# load.net
KiCad netlist of a schematic drawn in EAGLE
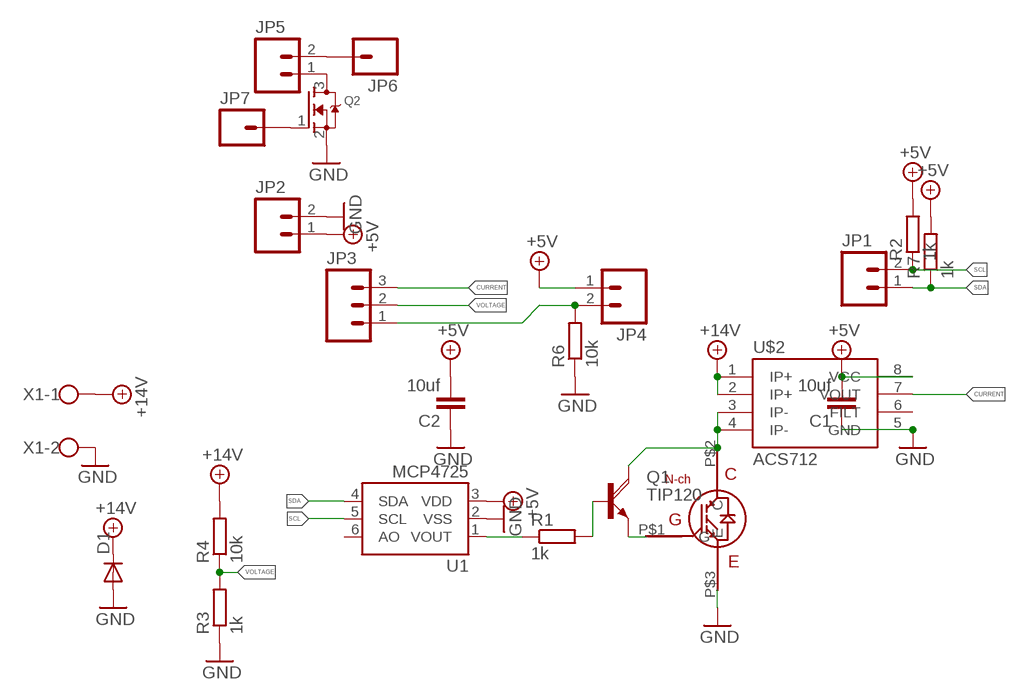
[diagram p0: schematic, sheet 1]

(export (version "E")
  (design (tool "Eeschema 10.0.6"))
  (components
    (comp (ref "C1")
      (value "10uf")
      (footprint "eagle-import:C0603")
      (libsource (lib "eagle-import") (part "C-EUC0603"))
    )
    (comp (ref "C2")
      (value "10uf")
      (footprint "eagle-import:C0603")
      (libsource (lib "eagle-import") (part "C-EUC0603"))
    )
    (comp (ref "D1")
      (value "DIODE-TO220V")
      (footprint "eagle-import:TO220ACS")
      (libsource (lib "eagle-import") (part "DIODE-TO220V"))
    )
    (comp (ref "JP1")
      (value "M02PTH")
      (footprint "eagle-import:1X02")
      (libsource (lib "eagle-import") (part "M02PTH"))
    )
    (comp (ref "JP2")
      (value "M02PTH")
      (footprint "eagle-import:1X02")
      (libsource (lib "eagle-import") (part "M02PTH"))
    )
    (comp (ref "JP3")
      (value "M03PTH")
      (footprint "eagle-import:1X03")
      (libsource (lib "eagle-import") (part "M03PTH"))
    )
    (comp (ref "JP4")
      (value "M02PTH")
      (footprint "eagle-import:1X02")
      (libsource (lib "eagle-import") (part "M02PTH"))
    )
    (comp (ref "JP5")
      (value "M02PTH")
      (footprint "eagle-import:1X02")
      (libsource (lib "eagle-import") (part "M02PTH"))
    )
    (comp (ref "JP6")
      (value "M01PTH")
      (footprint "eagle-import:1X01")
      (libsource (lib "eagle-import") (part "M01PTH"))
    )
    (comp (ref "JP7")
      (value "M01PTH")
      (footprint "eagle-import:1X01")
      (libsource (lib "eagle-import") (part "M01PTH"))
    )
    (comp (ref "Q1")
      (value "TIP120")
      (footprint "eagle-import:TO220AH")
      (libsource (lib "eagle-import") (part "TIP120"))
    )
    (comp (ref "Q2")
      (value "MOSFET-NREFLOW")
      (footprint "eagle-import:SOT23")
      (libsource (lib "eagle-import") (part "MOSFET-NREFLOW"))
    )
    (comp (ref "R1")
      (value "1k")
      (footprint "eagle-import:R0603")
      (libsource (lib "eagle-import") (part "R-EU_R0603"))
    )
    (comp (ref "R2")
      (value "1k")
      (footprint "eagle-import:R0603")
      (libsource (lib "eagle-import") (part "R-EU_R0603"))
    )
    (comp (ref "R3")
      (value "1k")
      (footprint "eagle-import:R0603")
      (libsource (lib "eagle-import") (part "R-EU_R0603"))
    )
    (comp (ref "R4")
      (value "10k")
      (footprint "eagle-import:R0603")
      (libsource (lib "eagle-import") (part "R-EU_R0603"))
    )
    (comp (ref "R6")
      (value "10k")
      (footprint "eagle-import:R0603")
      (libsource (lib "eagle-import") (part "R-EU_R0603"))
    )
    (comp (ref "R7")
      (value "1k")
      (footprint "eagle-import:R0603")
      (libsource (lib "eagle-import") (part "R-EU_R0603"))
    )
    (comp (ref "U$1")
      (value "TO-247A")
      (footprint "eagle-import:TO-247")
      (libsource (lib "eagle-import") (part "TO-247A"))
    )
    (comp (ref "U$2")
      (value "ACS712")
      (footprint "eagle-import:SO08")
      (libsource (lib "eagle-import") (part "ACS712"))
    )
    (comp (ref "U1")
      (value "MCP4725")
      (footprint "eagle-import:SOT23-6")
      (libsource (lib "eagle-import") (part "MCP4725SOT-23"))
    )
    (comp (ref "X1")
      (value "W237-102")
      (footprint "eagle-import:W237-102")
      (fields (field (name "MPN") "237-102"))
      (libsource (lib "eagle-import") (part "W237-102"))
    )
  )
  (nets
    (net (code "1") (name "+5V") (class "Default")
      (node (ref "C1") (pin "2") (pinfunction "2_2") (pintype "passive"))
      (node (ref "C2") (pin "2") (pinfunction "2_2") (pintype "passive"))
      (node (ref "JP2") (pin "1") (pinfunction "1_1") (pintype "passive"))
      (node (ref "JP4") (pin "1") (pinfunction "1_1") (pintype "passive"))
      (node (ref "R2") (pin "2") (pinfunction "2_2") (pintype "passive"))
      (node (ref "R7") (pin "2") (pinfunction "2_2") (pintype "passive"))
      (node (ref "U$2") (pin "8") (pinfunction "VCC_8") (pintype "bidirectional"))
      (node (ref "U1") (pin "3") (pinfunction "VDD_3") (pintype "bidirectional"))
    )
    (net (code "2") (name "+14V") (class "Default")
      (node (ref "D1") (pin "C") (pinfunction "C_C") (pintype "passive"))
      (node (ref "R4") (pin "2") (pinfunction "2_2") (pintype "passive"))
      (node (ref "U$2") (pin "1") (pinfunction "IP+_1") (pintype "bidirectional"))
      (node (ref "U$2") (pin "2") (pinfunction "IP+_2") (pintype "bidirectional"))
      (node (ref "X1") (pin "1") (pinfunction "KL_1") (pintype "passive"))
    )
    (net (code "3") (name "CURRENT") (class "Default")
      (node (ref "JP3") (pin "3") (pinfunction "3_3") (pintype "passive"))
      (node (ref "U$2") (pin "7") (pinfunction "VOUT_7") (pintype "bidirectional"))
    )
    (net (code "4") (name "GND") (class "Default")
      (node (ref "C1") (pin "1") (pinfunction "1_1") (pintype "passive"))
      (node (ref "C2") (pin "1") (pinfunction "1_1") (pintype "passive"))
      (node (ref "D1") (pin "A") (pinfunction "A_A") (pintype "passive"))
      (node (ref "JP2") (pin "2") (pinfunction "2_2") (pintype "passive"))
      (node (ref "Q2") (pin "2") (pinfunction "S_2") (pintype "bidirectional"))
      (node (ref "R3") (pin "1") (pinfunction "1_1") (pintype "passive"))
      (node (ref "R6") (pin "1") (pinfunction "1_1") (pintype "passive"))
      (node (ref "U$1") (pin "P$3") (pinfunction "E_P$3") (pintype "bidirectional"))
      (node (ref "U$2") (pin "5") (pinfunction "GND_5") (pintype "bidirectional"))
      (node (ref "U1") (pin "2") (pinfunction "VSS_2") (pintype "bidirectional"))
      (node (ref "X1") (pin "2") (pinfunction "KL_2") (pintype "passive"))
    )
    (net (code "5") (name "Net-(JP3-Pad1)") (class "Default")
      (node (ref "JP3") (pin "1") (pinfunction "1_1") (pintype "passive"))
      (node (ref "JP4") (pin "2") (pinfunction "2_2") (pintype "passive"))
      (node (ref "R6") (pin "2") (pinfunction "2_2") (pintype "passive"))
    )
    (net (code "6") (name "Net-(JP5-Pad2)") (class "Default")
      (node (ref "JP5") (pin "2") (pinfunction "2_2") (pintype "passive"))
      (node (ref "JP6") (pin "1") (pinfunction "1_1") (pintype "passive"))
    )
    (net (code "7") (name "Net-(Q1-PadB)") (class "Default")
      (node (ref "Q1") (pin "B") (pinfunction "B_B") (pintype "passive"))
      (node (ref "R1") (pin "2") (pinfunction "2_2") (pintype "passive"))
    )
    (net (code "8") (name "Net-(Q2-D)") (class "Default")
      (node (ref "JP5") (pin "1") (pinfunction "1_1") (pintype "passive"))
      (node (ref "Q2") (pin "3") (pinfunction "D_3") (pintype "bidirectional"))
    )
    (net (code "9") (name "Net-(Q2-G)") (class "Default")
      (node (ref "JP7") (pin "1") (pinfunction "1_1") (pintype "passive"))
      (node (ref "Q2") (pin "1") (pinfunction "G_1") (pintype "bidirectional"))
    )
    (net (code "10") (name "Net-(U$1-C)") (class "Default")
      (node (ref "Q1") (pin "C") (pinfunction "C_C") (pintype "passive"))
      (node (ref "U$1") (pin "P$2") (pinfunction "C_P$2") (pintype "bidirectional"))
      (node (ref "U$2") (pin "3") (pinfunction "IP-_3") (pintype "bidirectional"))
      (node (ref "U$2") (pin "4") (pinfunction "IP-_4") (pintype "bidirectional"))
    )
    (net (code "11") (name "Net-(U$1-G)") (class "Default")
      (node (ref "Q1") (pin "E") (pinfunction "E_E") (pintype "passive"))
      (node (ref "U$1") (pin "P$1") (pinfunction "G_P$1") (pintype "bidirectional"))
    )
    (net (code "12") (name "Net-(U1-VOUT)") (class "Default")
      (node (ref "R1") (pin "1") (pinfunction "1_1") (pintype "passive"))
      (node (ref "U1") (pin "1") (pinfunction "VOUT_1") (pintype "bidirectional"))
    )
    (net (code "13") (name "SCL") (class "Default")
      (node (ref "JP1") (pin "2") (pinfunction "2_2") (pintype "passive"))
      (node (ref "R2") (pin "1") (pinfunction "1_1") (pintype "passive"))
      (node (ref "U1") (pin "5") (pinfunction "SCL_5") (pintype "bidirectional"))
    )
    (net (code "14") (name "SDA") (class "Default")
      (node (ref "JP1") (pin "1") (pinfunction "1_1") (pintype "passive"))
      (node (ref "R7") (pin "1") (pinfunction "1_1") (pintype "passive"))
      (node (ref "U1") (pin "4") (pinfunction "SDA_4") (pintype "bidirectional"))
    )
    (net (code "15") (name "VOLTAGE") (class "Default")
      (node (ref "JP3") (pin "2") (pinfunction "2_2") (pintype "passive"))
      (node (ref "R3") (pin "2") (pinfunction "2_2") (pintype "passive"))
      (node (ref "R4") (pin "1") (pinfunction "1_1") (pintype "passive"))
    )
    (net (code "16") (name "unconnected-(U$2-FILT-Pad6)") (class "Default")
      (node (ref "U$2") (pin "6") (pinfunction "FILT_6") (pintype "bidirectional"))
    )
    (net (code "17") (name "unconnected-(U1-AO-Pad6)") (class "Default")
      (node (ref "U1") (pin "6") (pinfunction "AO_6") (pintype "bidirectional"))
    )
  )
)
